# spectrometer.net
KiCad netlist of a schematic drawn in EAGLE
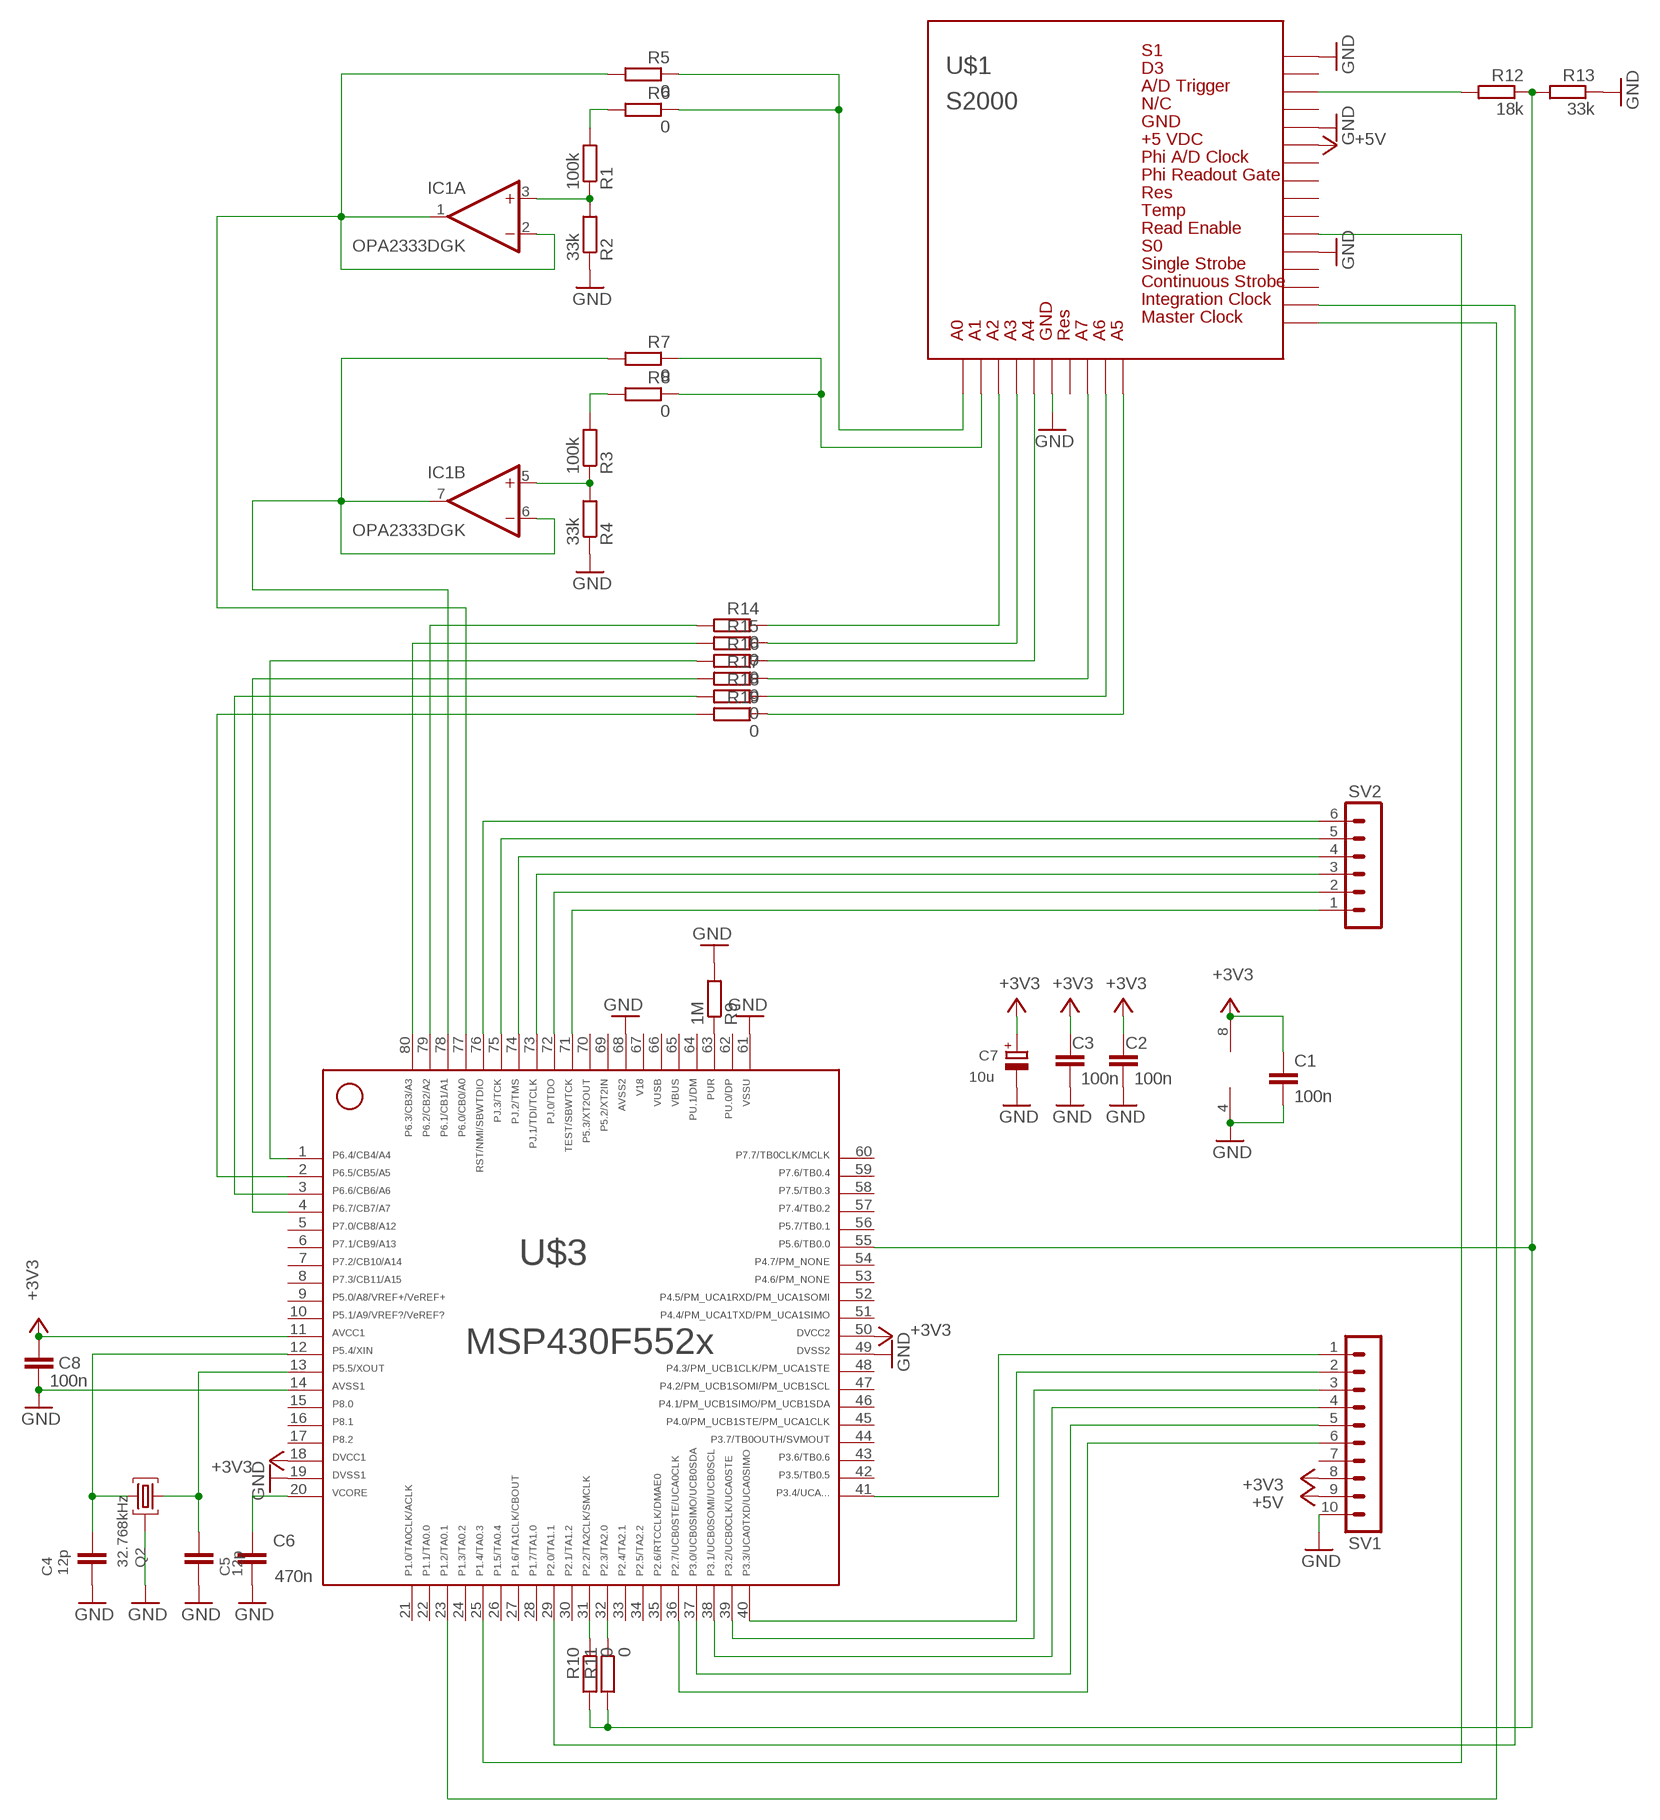
[diagram p0: schematic, sheet 1]

(export (version "E")
  (design (tool "Eeschema 10.0.6"))
  (components
    (comp (ref "C1")
      (value "100n")
      (footprint "eagle-import:C0603")
      (libsource (lib "eagle-import") (part "C-EUC0603"))
    )
    (comp (ref "C2")
      (value "100n")
      (footprint "eagle-import:C0603")
      (libsource (lib "eagle-import") (part "C-EUC0603"))
    )
    (comp (ref "C3")
      (value "100n")
      (footprint "eagle-import:C0603")
      (libsource (lib "eagle-import") (part "C-EUC0603"))
    )
    (comp (ref "C4")
      (value "12p")
      (footprint "eagle-import:C0603")
      (libsource (lib "eagle-import") (part "C-EUC0603"))
    )
    (comp (ref "C5")
      (value "12p")
      (footprint "eagle-import:C0603")
      (libsource (lib "eagle-import") (part "C-EUC0603"))
    )
    (comp (ref "C6")
      (value "470n")
      (footprint "eagle-import:C0603")
      (libsource (lib "eagle-import") (part "C-EUC0603"))
    )
    (comp (ref "C7")
      (value "10u")
      (footprint "eagle-import:A_3216-18R")
      (libsource (lib "eagle-import") (part "CPOL-EUA/3216-18R"))
    )
    (comp (ref "C8")
      (value "100n")
      (footprint "eagle-import:C0603")
      (libsource (lib "eagle-import") (part "C-EUC0603"))
    )
    (comp (ref "IC1")
      (value "OPA2333DGK")
      (footprint "eagle-import:MSOP08")
      (libsource (lib "eagle-import") (part "OPA2333DGK"))
    )
    (comp (ref "Q2")
      (value "32.768kHz")
      (footprint "eagle-import:MS3V-T1R")
      (libsource (lib "eagle-import") (part "MS3V-T1R"))
    )
    (comp (ref "R1")
      (value "100k")
      (footprint "eagle-import:R0603")
      (libsource (lib "eagle-import") (part "R-EU_R0603"))
    )
    (comp (ref "R2")
      (value "33k")
      (footprint "eagle-import:R0603")
      (libsource (lib "eagle-import") (part "R-EU_R0603"))
    )
    (comp (ref "R3")
      (value "100k")
      (footprint "eagle-import:R0603")
      (libsource (lib "eagle-import") (part "R-EU_R0603"))
    )
    (comp (ref "R4")
      (value "33k")
      (footprint "eagle-import:R0603")
      (libsource (lib "eagle-import") (part "R-EU_R0603"))
    )
    (comp (ref "R5")
      (value "0")
      (footprint "eagle-import:R0603")
      (libsource (lib "eagle-import") (part "R-EU_R0603"))
    )
    (comp (ref "R6")
      (value "0")
      (footprint "eagle-import:R0603")
      (libsource (lib "eagle-import") (part "R-EU_R0603"))
    )
    (comp (ref "R7")
      (value "0")
      (footprint "eagle-import:R0603")
      (libsource (lib "eagle-import") (part "R-EU_R0603"))
    )
    (comp (ref "R8")
      (value "0")
      (footprint "eagle-import:R0603")
      (libsource (lib "eagle-import") (part "R-EU_R0603"))
    )
    (comp (ref "R9")
      (value "1M")
      (footprint "eagle-import:R0603")
      (libsource (lib "eagle-import") (part "R-EU_R0603"))
    )
    (comp (ref "R10")
      (value "0")
      (footprint "eagle-import:R0603")
      (libsource (lib "eagle-import") (part "R-EU_R0603"))
    )
    (comp (ref "R11")
      (value "0")
      (footprint "eagle-import:R0603")
      (libsource (lib "eagle-import") (part "R-EU_R0603"))
    )
    (comp (ref "R12")
      (value "18k")
      (footprint "eagle-import:R0603")
      (libsource (lib "eagle-import") (part "R-EU_R0603"))
    )
    (comp (ref "R13")
      (value "33k")
      (footprint "eagle-import:R0603")
      (libsource (lib "eagle-import") (part "R-EU_R0603"))
    )
    (comp (ref "R14")
      (value "0")
      (footprint "eagle-import:R0603")
      (libsource (lib "eagle-import") (part "R-EU_R0603"))
    )
    (comp (ref "R15")
      (value "0")
      (footprint "eagle-import:R0603")
      (libsource (lib "eagle-import") (part "R-EU_R0603"))
    )
    (comp (ref "R16")
      (value "0")
      (footprint "eagle-import:R0603")
      (libsource (lib "eagle-import") (part "R-EU_R0603"))
    )
    (comp (ref "R17")
      (value "0")
      (footprint "eagle-import:R0603")
      (libsource (lib "eagle-import") (part "R-EU_R0603"))
    )
    (comp (ref "R18")
      (value "0")
      (footprint "eagle-import:R0603")
      (libsource (lib "eagle-import") (part "R-EU_R0603"))
    )
    (comp (ref "R19")
      (value "0")
      (footprint "eagle-import:R0603")
      (libsource (lib "eagle-import") (part "R-EU_R0603"))
    )
    (comp (ref "SV1")
      (value "MA10-1")
      (footprint "eagle-import:MA10-1")
      (libsource (lib "eagle-import") (part "MA10-1"))
    )
    (comp (ref "SV2")
      (value "MA06-1")
      (footprint "eagle-import:MA06-1")
      (libsource (lib "eagle-import") (part "MA06-1"))
    )
    (comp (ref "U$1")
      (value "S2000")
      (footprint "eagle-import:S2000")
      (libsource (lib "eagle-import") (part "S2000"))
    )
    (comp (ref "U$3")
      (value "F552X---PN80")
      (footprint "eagle-import:PN80")
      (libsource (lib "eagle-import") (part "F552X---PN80"))
    )
  )
  (nets
    (net (code "1") (name "+3V3") (class "Default")
      (node (ref "C1") (pin "1") (pinfunction "1_1") (pintype "passive"))
      (node (ref "C2") (pin "2") (pinfunction "2_2") (pintype "passive"))
      (node (ref "C3") (pin "2") (pinfunction "2_2") (pintype "passive"))
      (node (ref "C7") (pin "+") (pinfunction "+_+") (pintype "passive"))
      (node (ref "C8") (pin "1") (pinfunction "1_1") (pintype "passive"))
      (node (ref "IC1") (pin "8") (pinfunction "V+_8") (pintype "power_in"))
      (node (ref "SV1") (pin "8") (pinfunction "8_8") (pintype "passive"))
      (node (ref "U$3") (pin "11") (pinfunction "11_11") (pintype "power_in"))
      (node (ref "U$3") (pin "18") (pinfunction "18_18") (pintype "power_in"))
      (node (ref "U$3") (pin "50") (pinfunction "50_50") (pintype "power_in"))
    )
    (net (code "2") (name "+5V") (class "Default")
      (node (ref "SV1") (pin "9") (pinfunction "9_9") (pintype "passive"))
      (node (ref "U$1") (pin "H2$2") (pinfunction "H2$2_H2$2") (pintype "bidirectional"))
    )
    (net (code "3") (name "/65") (class "Default")
      (node (ref "U$3") (pin "65") (pinfunction "65_65") (pintype "power_in"))
    )
    (net (code "4") (name "/66") (class "Default")
      (node (ref "U$3") (pin "66") (pinfunction "66_66") (pintype "power_in"))
    )
    (net (code "5") (name "/67") (class "Default")
      (node (ref "U$3") (pin "67") (pinfunction "67_67") (pintype "power_in"))
    )
    (net (code "6") (name "GND") (class "Default")
      (node (ref "C1") (pin "2") (pinfunction "2_2") (pintype "passive"))
      (node (ref "C2") (pin "1") (pinfunction "1_1") (pintype "passive"))
      (node (ref "C3") (pin "1") (pinfunction "1_1") (pintype "passive"))
      (node (ref "C4") (pin "1") (pinfunction "1_1") (pintype "passive"))
      (node (ref "C5") (pin "1") (pinfunction "1_1") (pintype "passive"))
      (node (ref "C6") (pin "1") (pinfunction "1_1") (pintype "passive"))
      (node (ref "C7") (pin "-") (pinfunction "-_-") (pintype "passive"))
      (node (ref "C8") (pin "2") (pinfunction "2_2") (pintype "passive"))
      (node (ref "IC1") (pin "4") (pinfunction "V-_4") (pintype "power_in"))
      (node (ref "Q2") (pin "P3") (pinfunction "GND_P3") (pintype "power_in"))
      (node (ref "R13") (pin "1") (pinfunction "1_1") (pintype "passive"))
      (node (ref "R2") (pin "1") (pinfunction "1_1") (pintype "passive"))
      (node (ref "R4") (pin "1") (pinfunction "1_1") (pintype "passive"))
      (node (ref "R9") (pin "2") (pinfunction "2_2") (pintype "passive"))
      (node (ref "SV1") (pin "10") (pinfunction "10_10") (pintype "passive"))
      (node (ref "U$1") (pin "H1$6") (pinfunction "H1$6_H1$6") (pintype "bidirectional"))
      (node (ref "U$1") (pin "H2$1") (pinfunction "H2$1_H2$1") (pintype "bidirectional"))
      (node (ref "U$1") (pin "H2$8") (pinfunction "H2$8_H2$8") (pintype "bidirectional"))
      (node (ref "U$1") (pin "H2$A") (pinfunction "H2$A_H2$A") (pintype "bidirectional"))
      (node (ref "U$3") (pin "14") (pinfunction "14_14") (pintype "power_in"))
      (node (ref "U$3") (pin "19") (pinfunction "19_19") (pintype "power_in"))
      (node (ref "U$3") (pin "49") (pinfunction "49_49") (pintype "power_in"))
      (node (ref "U$3") (pin "61") (pinfunction "61_61") (pintype "power_in"))
      (node (ref "U$3") (pin "68") (pinfunction "68_68") (pintype "power_in"))
    )
    (net (code "7") (name "Net-(C6-Pad2)") (class "Default")
      (node (ref "C6") (pin "2") (pinfunction "2_2") (pintype "passive"))
      (node (ref "U$3") (pin "20") (pinfunction "20_20") (pintype "power_in"))
    )
    (net (code "8") (name "Net-(IC1A-+IN)") (class "Default")
      (node (ref "IC1") (pin "3") (pinfunction "+IN_3") (pintype "input"))
      (node (ref "R1") (pin "1") (pinfunction "1_1") (pintype "passive"))
      (node (ref "R2") (pin "2") (pinfunction "2_2") (pintype "passive"))
    )
    (net (code "9") (name "Net-(IC1A--IN)") (class "Default")
      (node (ref "IC1") (pin "1") (pinfunction "OUT_1") (pintype "output"))
      (node (ref "IC1") (pin "2") (pinfunction "-IN_2") (pintype "input"))
      (node (ref "R5") (pin "2") (pinfunction "2_2") (pintype "passive"))
      (node (ref "U$3") (pin "77") (pinfunction "77_77") (pintype "bidirectional"))
    )
    (net (code "10") (name "Net-(IC1B-+IN)") (class "Default")
      (node (ref "IC1") (pin "5") (pinfunction "+IN_5") (pintype "input"))
      (node (ref "R3") (pin "1") (pinfunction "1_1") (pintype "passive"))
      (node (ref "R4") (pin "2") (pinfunction "2_2") (pintype "passive"))
    )
    (net (code "11") (name "Net-(IC1B--IN)") (class "Default")
      (node (ref "IC1") (pin "6") (pinfunction "-IN_6") (pintype "input"))
      (node (ref "IC1") (pin "7") (pinfunction "OUT_7") (pintype "output"))
      (node (ref "R7") (pin "2") (pinfunction "2_2") (pintype "passive"))
      (node (ref "U$3") (pin "78") (pinfunction "78_78") (pintype "bidirectional"))
    )
    (net (code "12") (name "Net-(Q2-1)") (class "Default")
      (node (ref "C5") (pin "2") (pinfunction "2_2") (pintype "passive"))
      (node (ref "Q2") (pin "P1") (pinfunction "1_P1") (pintype "bidirectional"))
      (node (ref "U$3") (pin "13") (pinfunction "13_13") (pintype "bidirectional"))
    )
    (net (code "13") (name "Net-(Q2-2)") (class "Default")
      (node (ref "C4") (pin "2") (pinfunction "2_2") (pintype "passive"))
      (node (ref "Q2") (pin "P2") (pinfunction "2_P2") (pintype "bidirectional"))
      (node (ref "U$3") (pin "12") (pinfunction "12_12") (pintype "bidirectional"))
    )
    (net (code "14") (name "Net-(R1-Pad2)") (class "Default")
      (node (ref "R1") (pin "2") (pinfunction "2_2") (pintype "passive"))
      (node (ref "R6") (pin "2") (pinfunction "2_2") (pintype "passive"))
    )
    (net (code "15") (name "Net-(R3-Pad2)") (class "Default")
      (node (ref "R3") (pin "2") (pinfunction "2_2") (pintype "passive"))
      (node (ref "R8") (pin "2") (pinfunction "2_2") (pintype "passive"))
    )
    (net (code "16") (name "Net-(R5-Pad1)") (class "Default")
      (node (ref "R5") (pin "1") (pinfunction "1_1") (pintype "passive"))
      (node (ref "R6") (pin "1") (pinfunction "1_1") (pintype "passive"))
      (node (ref "U$1") (pin "H1$1") (pinfunction "H1$1_H1$1") (pintype "bidirectional"))
    )
    (net (code "17") (name "Net-(R7-Pad1)") (class "Default")
      (node (ref "R7") (pin "1") (pinfunction "1_1") (pintype "passive"))
      (node (ref "R8") (pin "1") (pinfunction "1_1") (pintype "passive"))
      (node (ref "U$1") (pin "H1$2") (pinfunction "H1$2_H1$2") (pintype "bidirectional"))
    )
    (net (code "18") (name "Net-(R9-Pad1)") (class "Default")
      (node (ref "R9") (pin "1") (pinfunction "1_1") (pintype "passive"))
      (node (ref "U$3") (pin "63") (pinfunction "63_63") (pintype "bidirectional"))
    )
    (net (code "19") (name "Net-(R10-Pad1)") (class "Default")
      (node (ref "R10") (pin "1") (pinfunction "1_1") (pintype "passive"))
      (node (ref "U$3") (pin "31") (pinfunction "31_31") (pintype "bidirectional"))
    )
    (net (code "20") (name "Net-(R10-Pad2)") (class "Default")
      (node (ref "R10") (pin "2") (pinfunction "2_2") (pintype "passive"))
      (node (ref "R11") (pin "2") (pinfunction "2_2") (pintype "passive"))
      (node (ref "R12") (pin "1") (pinfunction "1_1") (pintype "passive"))
      (node (ref "R13") (pin "2") (pinfunction "2_2") (pintype "passive"))
      (node (ref "U$3") (pin "55") (pinfunction "55_55") (pintype "bidirectional"))
    )
    (net (code "21") (name "Net-(R11-Pad1)") (class "Default")
      (node (ref "R11") (pin "1") (pinfunction "1_1") (pintype "passive"))
      (node (ref "U$3") (pin "32") (pinfunction "32_32") (pintype "bidirectional"))
    )
    (net (code "22") (name "Net-(R12-Pad2)") (class "Default")
      (node (ref "R12") (pin "2") (pinfunction "2_2") (pintype "passive"))
      (node (ref "U$1") (pin "H2$C") (pinfunction "H2$C_H2$C") (pintype "bidirectional"))
    )
    (net (code "23") (name "Net-(R14-Pad1)") (class "Default")
      (node (ref "R14") (pin "1") (pinfunction "1_1") (pintype "passive"))
      (node (ref "U$1") (pin "H1$3") (pinfunction "H1$3_H1$3") (pintype "bidirectional"))
    )
    (net (code "24") (name "Net-(R14-Pad2)") (class "Default")
      (node (ref "R14") (pin "2") (pinfunction "2_2") (pintype "passive"))
      (node (ref "U$3") (pin "79") (pinfunction "79_79") (pintype "bidirectional"))
    )
    (net (code "25") (name "Net-(R15-Pad1)") (class "Default")
      (node (ref "R15") (pin "1") (pinfunction "1_1") (pintype "passive"))
      (node (ref "U$1") (pin "H1$4") (pinfunction "H1$4_H1$4") (pintype "bidirectional"))
    )
    (net (code "26") (name "Net-(R15-Pad2)") (class "Default")
      (node (ref "R15") (pin "2") (pinfunction "2_2") (pintype "passive"))
      (node (ref "U$3") (pin "80") (pinfunction "80_80") (pintype "bidirectional"))
    )
    (net (code "27") (name "Net-(R16-Pad1)") (class "Default")
      (node (ref "R16") (pin "1") (pinfunction "1_1") (pintype "passive"))
      (node (ref "U$1") (pin "H1$5") (pinfunction "H1$5_H1$5") (pintype "bidirectional"))
    )
    (net (code "28") (name "Net-(R16-Pad2)") (class "Default")
      (node (ref "R16") (pin "2") (pinfunction "2_2") (pintype "passive"))
      (node (ref "U$3") (pin "1") (pinfunction "1_1") (pintype "bidirectional"))
    )
    (net (code "29") (name "Net-(R17-Pad1)") (class "Default")
      (node (ref "R17") (pin "1") (pinfunction "1_1") (pintype "passive"))
      (node (ref "U$1") (pin "H1$8") (pinfunction "H1$8_H1$8") (pintype "bidirectional"))
    )
    (net (code "30") (name "Net-(R17-Pad2)") (class "Default")
      (node (ref "R17") (pin "2") (pinfunction "2_2") (pintype "passive"))
      (node (ref "U$3") (pin "4") (pinfunction "4_4") (pintype "bidirectional"))
    )
    (net (code "31") (name "Net-(R18-Pad1)") (class "Default")
      (node (ref "R18") (pin "1") (pinfunction "1_1") (pintype "passive"))
      (node (ref "U$1") (pin "H1$9") (pinfunction "H1$9_H1$9") (pintype "bidirectional"))
    )
    (net (code "32") (name "Net-(R18-Pad2)") (class "Default")
      (node (ref "R18") (pin "2") (pinfunction "2_2") (pintype "passive"))
      (node (ref "U$3") (pin "3") (pinfunction "3_3") (pintype "bidirectional"))
    )
    (net (code "33") (name "Net-(R19-Pad1)") (class "Default")
      (node (ref "R19") (pin "1") (pinfunction "1_1") (pintype "passive"))
      (node (ref "U$1") (pin "H1$10") (pinfunction "H1$10_H1$10") (pintype "bidirectional"))
    )
    (net (code "34") (name "Net-(R19-Pad2)") (class "Default")
      (node (ref "R19") (pin "2") (pinfunction "2_2") (pintype "passive"))
      (node (ref "U$3") (pin "2") (pinfunction "2_2") (pintype "bidirectional"))
    )
    (net (code "35") (name "Net-(SV1-Pad1)") (class "Default")
      (node (ref "SV1") (pin "1") (pinfunction "1_1") (pintype "passive"))
      (node (ref "U$3") (pin "41") (pinfunction "41_41") (pintype "bidirectional"))
    )
    (net (code "36") (name "Net-(SV1-Pad2)") (class "Default")
      (node (ref "SV1") (pin "2") (pinfunction "2_2") (pintype "passive"))
      (node (ref "U$3") (pin "40") (pinfunction "40_40") (pintype "bidirectional"))
    )
    (net (code "37") (name "Net-(SV1-Pad3)") (class "Default")
      (node (ref "SV1") (pin "3") (pinfunction "3_3") (pintype "passive"))
      (node (ref "U$3") (pin "39") (pinfunction "39_39") (pintype "bidirectional"))
    )
    (net (code "38") (name "Net-(SV1-Pad4)") (class "Default")
      (node (ref "SV1") (pin "4") (pinfunction "4_4") (pintype "passive"))
      (node (ref "U$3") (pin "38") (pinfunction "38_38") (pintype "bidirectional"))
    )
    (net (code "39") (name "Net-(SV1-Pad5)") (class "Default")
      (node (ref "SV1") (pin "5") (pinfunction "5_5") (pintype "passive"))
      (node (ref "U$3") (pin "37") (pinfunction "37_37") (pintype "bidirectional"))
    )
    (net (code "40") (name "Net-(SV1-Pad6)") (class "Default")
      (node (ref "SV1") (pin "6") (pinfunction "6_6") (pintype "passive"))
      (node (ref "U$3") (pin "36") (pinfunction "36_36") (pintype "bidirectional"))
    )
    (net (code "41") (name "Net-(SV2-Pad1)") (class "Default")
      (node (ref "SV2") (pin "1") (pinfunction "1_1") (pintype "passive"))
      (node (ref "U$3") (pin "71") (pinfunction "71_71") (pintype "input"))
    )
    (net (code "42") (name "Net-(SV2-Pad2)") (class "Default")
      (node (ref "SV2") (pin "2") (pinfunction "2_2") (pintype "passive"))
      (node (ref "U$3") (pin "72") (pinfunction "72_72") (pintype "bidirectional"))
    )
    (net (code "43") (name "Net-(SV2-Pad3)") (class "Default")
      (node (ref "SV2") (pin "3") (pinfunction "3_3") (pintype "passive"))
      (node (ref "U$3") (pin "73") (pinfunction "73_73") (pintype "bidirectional"))
    )
    (net (code "44") (name "Net-(SV2-Pad4)") (class "Default")
      (node (ref "SV2") (pin "4") (pinfunction "4_4") (pintype "passive"))
      (node (ref "U$3") (pin "74") (pinfunction "74_74") (pintype "bidirectional"))
    )
    (net (code "45") (name "Net-(SV2-Pad5)") (class "Default")
      (node (ref "SV2") (pin "5") (pinfunction "5_5") (pintype "passive"))
      (node (ref "U$3") (pin "75") (pinfunction "75_75") (pintype "bidirectional"))
    )
    (net (code "46") (name "Net-(SV2-Pad6)") (class "Default")
      (node (ref "SV2") (pin "6") (pinfunction "6_6") (pintype "passive"))
      (node (ref "U$3") (pin "76") (pinfunction "76_76") (pintype "bidirectional"))
    )
    (net (code "47") (name "Net-(U$1-PadH2$7)") (class "Default")
      (node (ref "U$1") (pin "H2$7") (pinfunction "H2$7_H2$7") (pintype "bidirectional"))
      (node (ref "U$3") (pin "25") (pinfunction "25_25") (pintype "bidirectional"))
    )
    (net (code "48") (name "Net-(U$1-PadH2$11)") (class "Default")
      (node (ref "U$1") (pin "H2$11") (pinfunction "H2$11_H2$11") (pintype "bidirectional"))
      (node (ref "U$3") (pin "29") (pinfunction "29_29") (pintype "bidirectional"))
    )
    (net (code "49") (name "Net-(U$1-PadH2$12)") (class "Default")
      (node (ref "U$1") (pin "H2$12") (pinfunction "H2$12_H2$12") (pintype "bidirectional"))
      (node (ref "U$3") (pin "23") (pinfunction "23_23") (pintype "bidirectional"))
    )
    (net (code "50") (name "unconnected-(SV1-Pad7)") (class "Default")
      (node (ref "SV1") (pin "7") (pinfunction "7_7") (pintype "passive"))
    )
    (net (code "51") (name "unconnected-(U$1-PadH1$7)") (class "Default")
      (node (ref "U$1") (pin "H1$7") (pinfunction "H1$7_H1$7") (pintype "bidirectional"))
    )
    (net (code "52") (name "unconnected-(U$1-PadH2$3)") (class "Default")
      (node (ref "U$1") (pin "H2$3") (pinfunction "H2$3_H2$3") (pintype "bidirectional"))
    )
    (net (code "53") (name "unconnected-(U$1-PadH2$4)") (class "Default")
      (node (ref "U$1") (pin "H2$4") (pinfunction "H2$4_H2$4") (pintype "bidirectional"))
    )
    (net (code "54") (name "unconnected-(U$1-PadH2$5)") (class "Default")
      (node (ref "U$1") (pin "H2$5") (pinfunction "H2$5_H2$5") (pintype "bidirectional"))
    )
    (net (code "55") (name "unconnected-(U$1-PadH2$6)") (class "Default")
      (node (ref "U$1") (pin "H2$6") (pinfunction "H2$6_H2$6") (pintype "bidirectional"))
    )
    (net (code "56") (name "unconnected-(U$1-PadH2$9)") (class "Default")
      (node (ref "U$1") (pin "H2$9") (pinfunction "H2$9_H2$9") (pintype "bidirectional"))
    )
    (net (code "57") (name "unconnected-(U$1-PadH2$10)") (class "Default")
      (node (ref "U$1") (pin "H2$10") (pinfunction "H2$10_H2$10") (pintype "bidirectional"))
    )
    (net (code "58") (name "unconnected-(U$1-PadH2$B)") (class "Default")
      (node (ref "U$1") (pin "H2$B") (pinfunction "H2$B_H2$B") (pintype "bidirectional"))
    )
    (net (code "59") (name "unconnected-(U$1-PadH2$D)") (class "Default")
      (node (ref "U$1") (pin "H2$D") (pinfunction "H2$D_H2$D") (pintype "bidirectional"))
    )
    (net (code "60") (name "unconnected-(U$3-Pad5)") (class "Default")
      (node (ref "U$3") (pin "5") (pinfunction "5_5") (pintype "bidirectional"))
    )
    (net (code "61") (name "unconnected-(U$3-Pad6)") (class "Default")
      (node (ref "U$3") (pin "6") (pinfunction "6_6") (pintype "bidirectional"))
    )
    (net (code "62") (name "unconnected-(U$3-Pad7)") (class "Default")
      (node (ref "U$3") (pin "7") (pinfunction "7_7") (pintype "bidirectional"))
    )
    (net (code "63") (name "unconnected-(U$3-Pad8)") (class "Default")
      (node (ref "U$3") (pin "8") (pinfunction "8_8") (pintype "bidirectional"))
    )
    (net (code "64") (name "unconnected-(U$3-Pad9)") (class "Default")
      (node (ref "U$3") (pin "9") (pinfunction "9_9") (pintype "bidirectional"))
    )
    (net (code "65") (name "unconnected-(U$3-Pad10)") (class "Default")
      (node (ref "U$3") (pin "10") (pinfunction "10_10") (pintype "bidirectional"))
    )
    (net (code "66") (name "unconnected-(U$3-Pad15)") (class "Default")
      (node (ref "U$3") (pin "15") (pinfunction "15_15") (pintype "bidirectional"))
    )
    (net (code "67") (name "unconnected-(U$3-Pad16)") (class "Default")
      (node (ref "U$3") (pin "16") (pinfunction "16_16") (pintype "bidirectional"))
    )
    (net (code "68") (name "unconnected-(U$3-Pad17)") (class "Default")
      (node (ref "U$3") (pin "17") (pinfunction "17_17") (pintype "bidirectional"))
    )
    (net (code "69") (name "unconnected-(U$3-Pad21)") (class "Default")
      (node (ref "U$3") (pin "21") (pinfunction "21_21") (pintype "bidirectional"))
    )
    (net (code "70") (name "unconnected-(U$3-Pad22)") (class "Default")
      (node (ref "U$3") (pin "22") (pinfunction "22_22") (pintype "bidirectional"))
    )
    (net (code "71") (name "unconnected-(U$3-Pad24)") (class "Default")
      (node (ref "U$3") (pin "24") (pinfunction "24_24") (pintype "bidirectional"))
    )
    (net (code "72") (name "unconnected-(U$3-Pad26)") (class "Default")
      (node (ref "U$3") (pin "26") (pinfunction "26_26") (pintype "bidirectional"))
    )
    (net (code "73") (name "unconnected-(U$3-Pad27)") (class "Default")
      (node (ref "U$3") (pin "27") (pinfunction "27_27") (pintype "bidirectional"))
    )
    (net (code "74") (name "unconnected-(U$3-Pad28)") (class "Default")
      (node (ref "U$3") (pin "28") (pinfunction "28_28") (pintype "bidirectional"))
    )
    (net (code "75") (name "unconnected-(U$3-Pad30)") (class "Default")
      (node (ref "U$3") (pin "30") (pinfunction "30_30") (pintype "bidirectional"))
    )
    (net (code "76") (name "unconnected-(U$3-Pad33)") (class "Default")
      (node (ref "U$3") (pin "33") (pinfunction "33_33") (pintype "bidirectional"))
    )
    (net (code "77") (name "unconnected-(U$3-Pad34)") (class "Default")
      (node (ref "U$3") (pin "34") (pinfunction "34_34") (pintype "bidirectional"))
    )
    (net (code "78") (name "unconnected-(U$3-Pad35)") (class "Default")
      (node (ref "U$3") (pin "35") (pinfunction "35_35") (pintype "bidirectional"))
    )
    (net (code "79") (name "unconnected-(U$3-Pad42)") (class "Default")
      (node (ref "U$3") (pin "42") (pinfunction "42_42") (pintype "bidirectional"))
    )
    (net (code "80") (name "unconnected-(U$3-Pad43)") (class "Default")
      (node (ref "U$3") (pin "43") (pinfunction "43_43") (pintype "bidirectional"))
    )
    (net (code "81") (name "unconnected-(U$3-Pad44)") (class "Default")
      (node (ref "U$3") (pin "44") (pinfunction "44_44") (pintype "bidirectional"))
    )
    (net (code "82") (name "unconnected-(U$3-Pad45)") (class "Default")
      (node (ref "U$3") (pin "45") (pinfunction "45_45") (pintype "bidirectional"))
    )
    (net (code "83") (name "unconnected-(U$3-Pad46)") (class "Default")
      (node (ref "U$3") (pin "46") (pinfunction "46_46") (pintype "bidirectional"))
    )
    (net (code "84") (name "unconnected-(U$3-Pad47)") (class "Default")
      (node (ref "U$3") (pin "47") (pinfunction "47_47") (pintype "bidirectional"))
    )
    (net (code "85") (name "unconnected-(U$3-Pad48)") (class "Default")
      (node (ref "U$3") (pin "48") (pinfunction "48_48") (pintype "bidirectional"))
    )
    (net (code "86") (name "unconnected-(U$3-Pad51)") (class "Default")
      (node (ref "U$3") (pin "51") (pinfunction "51_51") (pintype "bidirectional"))
    )
    (net (code "87") (name "unconnected-(U$3-Pad52)") (class "Default")
      (node (ref "U$3") (pin "52") (pinfunction "52_52") (pintype "bidirectional"))
    )
    (net (code "88") (name "unconnected-(U$3-Pad53)") (class "Default")
      (node (ref "U$3") (pin "53") (pinfunction "53_53") (pintype "bidirectional"))
    )
    (net (code "89") (name "unconnected-(U$3-Pad54)") (class "Default")
      (node (ref "U$3") (pin "54") (pinfunction "54_54") (pintype "bidirectional"))
    )
    (net (code "90") (name "unconnected-(U$3-Pad56)") (class "Default")
      (node (ref "U$3") (pin "56") (pinfunction "56_56") (pintype "bidirectional"))
    )
    (net (code "91") (name "unconnected-(U$3-Pad57)") (class "Default")
      (node (ref "U$3") (pin "57") (pinfunction "57_57") (pintype "bidirectional"))
    )
    (net (code "92") (name "unconnected-(U$3-Pad58)") (class "Default")
      (node (ref "U$3") (pin "58") (pinfunction "58_58") (pintype "bidirectional"))
    )
    (net (code "93") (name "unconnected-(U$3-Pad59)") (class "Default")
      (node (ref "U$3") (pin "59") (pinfunction "59_59") (pintype "bidirectional"))
    )
    (net (code "94") (name "unconnected-(U$3-Pad60)") (class "Default")
      (node (ref "U$3") (pin "60") (pinfunction "60_60") (pintype "bidirectional"))
    )
    (net (code "95") (name "unconnected-(U$3-Pad62)") (class "Default")
      (node (ref "U$3") (pin "62") (pinfunction "62_62") (pintype "bidirectional"))
    )
    (net (code "96") (name "unconnected-(U$3-Pad64)") (class "Default")
      (node (ref "U$3") (pin "64") (pinfunction "64_64") (pintype "bidirectional"))
    )
    (net (code "97") (name "unconnected-(U$3-Pad69)") (class "Default")
      (node (ref "U$3") (pin "69") (pinfunction "69_69") (pintype "bidirectional"))
    )
    (net (code "98") (name "unconnected-(U$3-Pad70)") (class "Default")
      (node (ref "U$3") (pin "70") (pinfunction "70_70") (pintype "bidirectional"))
    )
  )
)
